# 7Seg.net
KiCad netlist of a schematic drawn in Altium Designer
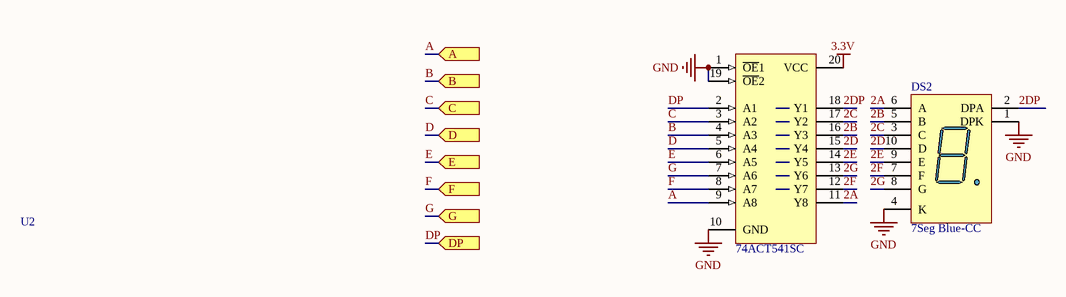
[diagram p0: 7Seg.SchDoc]

(export (version "E")
  (design (tool "Eeschema 10.0.6"))
  (components
    (comp (ref "DS2")
      (value "7Seg Blue-CC")
      (footprint "7Segment Small")
      (description "14.2 mm General Purpose Blue 7-Segment Display: CC, RH DP, Gray Surface")
      (fields (field (name "PUBLISHER") "Altium Limited"))
      (libsource (lib "KN2CLib") (part "7Seg Blue-CC_1"))
    )
    (comp (ref "U2")
      (value "74ACT541SC")
      (footprint "M20B_M")
      (description "Octal Buffer/Line Driver with 3-State Output")
      (fields (field (name "PUBLISHER") "Altium Limited"))
      (libsource (lib "FSC Logic Buffer Line Driver") (part "74ACT541SC"))
    )
  )
  (nets
    (net (code "1") (name "/2A") (class "Default")
      (node (ref "DS2") (pin "6") (pinfunction "A_6") (pintype "passive"))
      (node (ref "U2") (pin "11") (pinfunction "Y8_11") (pintype "tri_state"))
    )
    (net (code "2") (name "/2B") (class "Default")
      (node (ref "DS2") (pin "5") (pinfunction "B_5") (pintype "passive"))
      (node (ref "U2") (pin "16") (pinfunction "Y3_16") (pintype "tri_state"))
    )
    (net (code "3") (name "/2C") (class "Default")
      (node (ref "DS2") (pin "3") (pinfunction "C_3") (pintype "passive"))
      (node (ref "U2") (pin "17") (pinfunction "Y2_17") (pintype "tri_state"))
    )
    (net (code "4") (name "/2D") (class "Default")
      (node (ref "DS2") (pin "10") (pinfunction "D_10") (pintype "passive"))
      (node (ref "U2") (pin "15") (pinfunction "Y4_15") (pintype "tri_state"))
    )
    (net (code "5") (name "/2DP") (class "Default")
      (node (ref "DS2") (pin "2") (pinfunction "DPA_2") (pintype "passive"))
      (node (ref "U2") (pin "18") (pinfunction "Y1_18") (pintype "tri_state"))
    )
    (net (code "6") (name "/2E") (class "Default")
      (node (ref "DS2") (pin "9") (pinfunction "E_9") (pintype "passive"))
      (node (ref "U2") (pin "14") (pinfunction "Y5_14") (pintype "tri_state"))
    )
    (net (code "7") (name "/2F") (class "Default")
      (node (ref "DS2") (pin "7") (pinfunction "F_7") (pintype "passive"))
      (node (ref "U2") (pin "12") (pinfunction "Y7_12") (pintype "tri_state"))
    )
    (net (code "8") (name "/2G") (class "Default")
      (node (ref "DS2") (pin "8") (pinfunction "G_8") (pintype "passive"))
      (node (ref "U2") (pin "13") (pinfunction "Y6_13") (pintype "tri_state"))
    )
    (net (code "9") (name "/A") (class "Default")
      (node (ref "U2") (pin "9") (pinfunction "A8_9") (pintype "input"))
    )
    (net (code "10") (name "/B") (class "Default")
      (node (ref "U2") (pin "4") (pinfunction "A3_4") (pintype "input"))
    )
    (net (code "11") (name "/C") (class "Default")
      (node (ref "U2") (pin "3") (pinfunction "A2_3") (pintype "input"))
    )
    (net (code "12") (name "/D") (class "Default")
      (node (ref "U2") (pin "5") (pinfunction "A4_5") (pintype "input"))
    )
    (net (code "13") (name "/DP") (class "Default")
      (node (ref "U2") (pin "2") (pinfunction "A1_2") (pintype "input"))
    )
    (net (code "14") (name "/E") (class "Default")
      (node (ref "U2") (pin "6") (pinfunction "A5_6") (pintype "input"))
    )
    (net (code "15") (name "/F") (class "Default")
      (node (ref "U2") (pin "8") (pinfunction "A7_8") (pintype "input"))
    )
    (net (code "16") (name "/G") (class "Default")
      (node (ref "U2") (pin "7") (pinfunction "A6_7") (pintype "input"))
    )
    (net (code "17") (name "3.3V") (class "Default")
      (node (ref "U2") (pin "20") (pinfunction "VCC_20") (pintype "power_in"))
    )
    (net (code "18") (name "GND") (class "Default")
      (node (ref "DS2") (pin "1") (pinfunction "DPK_1") (pintype "passive"))
      (node (ref "DS2") (pin "4") (pinfunction "K_4") (pintype "passive"))
      (node (ref "U2") (pin "1") (pinfunction "~{OE}1_1") (pintype "input"))
      (node (ref "U2") (pin "10") (pinfunction "GND_10") (pintype "power_in"))
      (node (ref "U2") (pin "19") (pinfunction "~{OE}2_19") (pintype "input"))
    )
  )
)
